# mkuBoard-044-3B.net
KiCad netlist of a schematic drawn in EAGLE
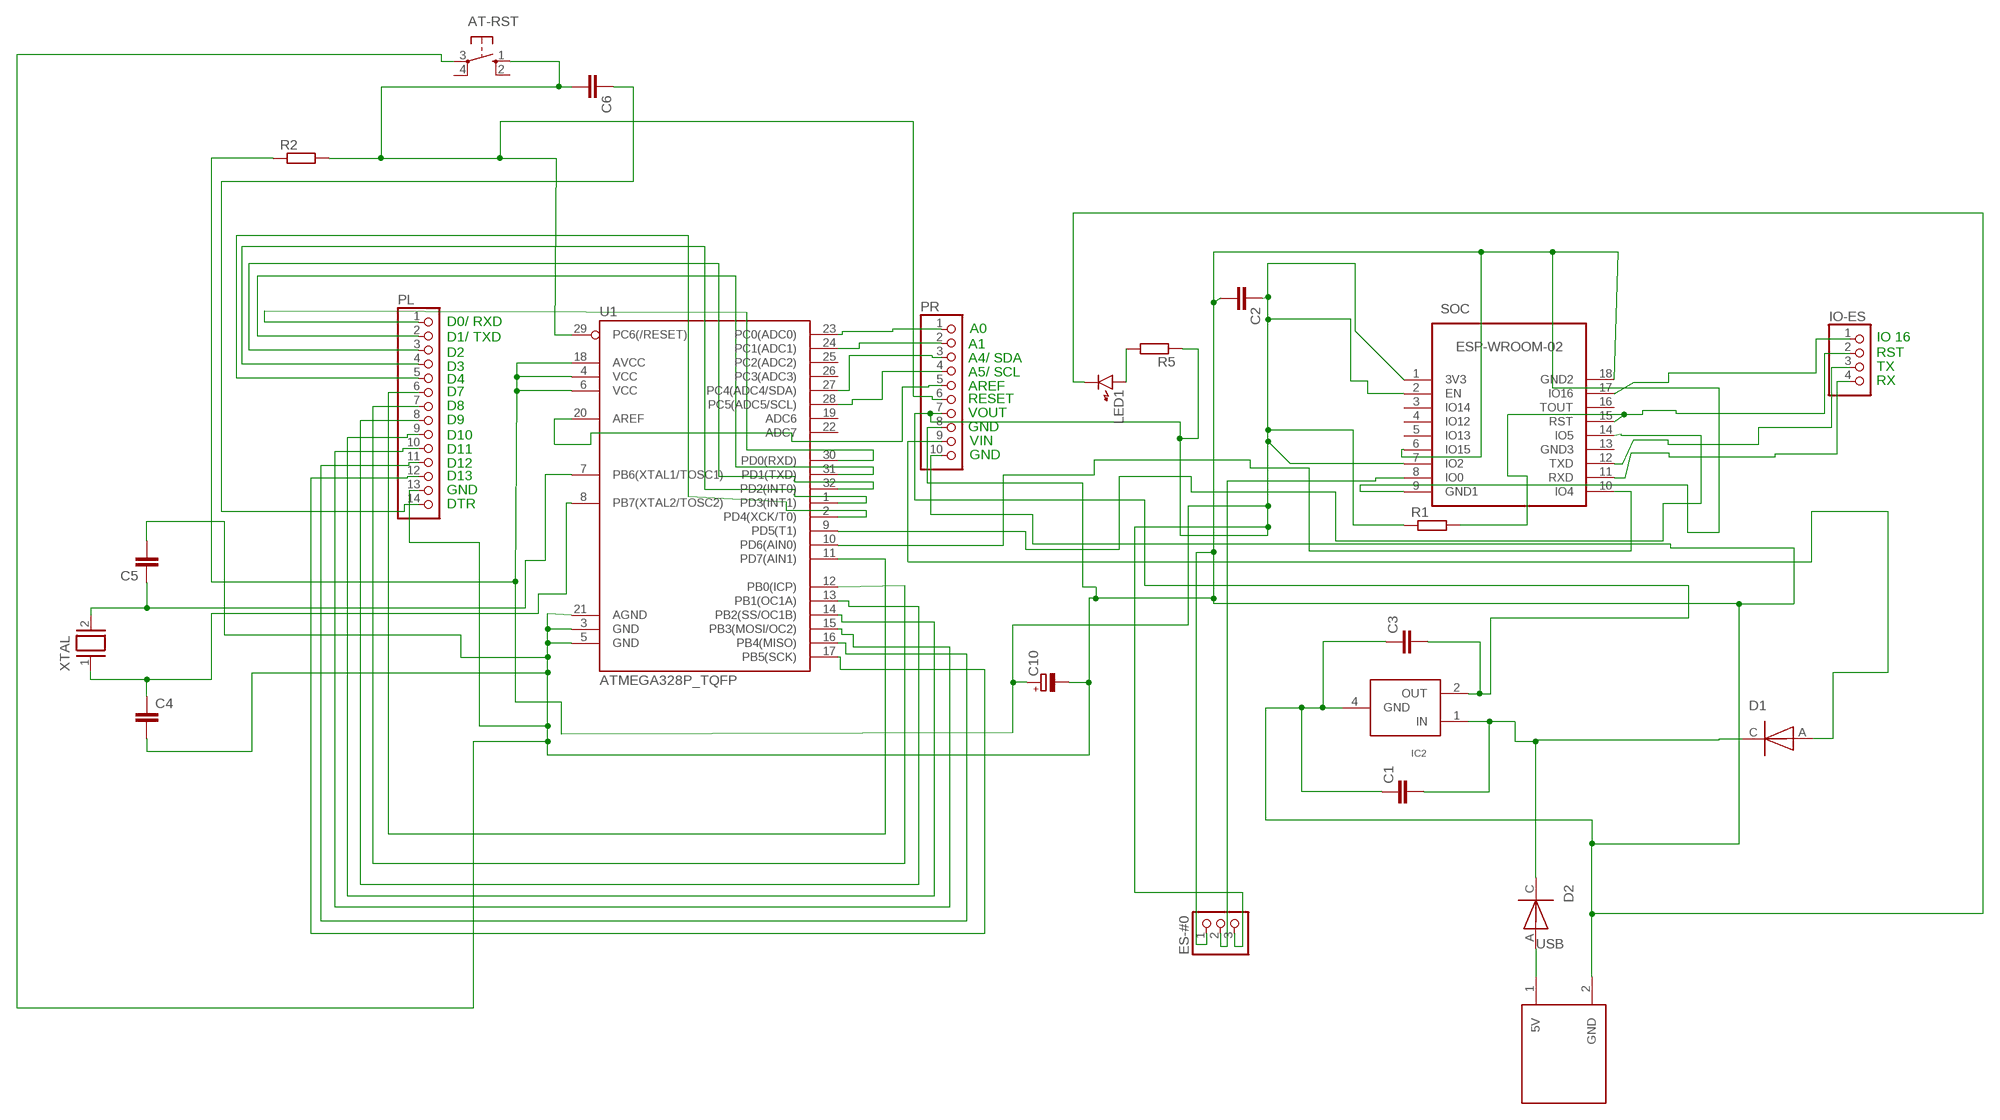
[diagram p0: schematic, sheet 1]

(export (version "E")
  (design (tool "Eeschema 10.0.6"))
  (components
    (comp (ref "AT-RST")
      (value "10-XX")
      (footprint "eagle-import:B3F-10XX")
      (fields (field (name "MPN") "B3F-1000"))
      (libsource (lib "eagle-import") (part "10-XX"))
    )
    (comp (ref "C1")
      (value "C-EUC0603")
      (footprint "eagle-import:C0603")
      (libsource (lib "eagle-import") (part "C-EUC0603"))
    )
    (comp (ref "C2")
      (value "C-EUC0603")
      (footprint "eagle-import:C0603")
      (libsource (lib "eagle-import") (part "C-EUC0603"))
    )
    (comp (ref "C3")
      (value "C-EUC1206")
      (footprint "eagle-import:C1206")
      (libsource (lib "eagle-import") (part "C-EUC1206"))
    )
    (comp (ref "C4")
      (value "C-EUC0603")
      (footprint "eagle-import:C0603")
      (libsource (lib "eagle-import") (part "C-EUC0603"))
    )
    (comp (ref "C5")
      (value "C-EUC0603")
      (footprint "eagle-import:C0603")
      (libsource (lib "eagle-import") (part "C-EUC0603"))
    )
    (comp (ref "C6")
      (value "C-EUC0603")
      (footprint "eagle-import:C0603")
      (libsource (lib "eagle-import") (part "C-EUC0603"))
    )
    (comp (ref "C10")
      (value "CPOL-EU153CLV-0605")
      (footprint "eagle-import:153CLV-0605")
      (libsource (lib "eagle-import") (part "CPOL-EU153CLV-0605"))
    )
    (comp (ref "D1")
      (value "DIODE-EX")
      (footprint "eagle-import:SOD80C")
      (libsource (lib "eagle-import") (part "DIODE-EX"))
    )
    (comp (ref "D2")
      (value "DIODE-EX")
      (footprint "eagle-import:SOD80C")
      (libsource (lib "eagle-import") (part "DIODE-EX"))
    )
    (comp (ref "ES-#0")
      (value "PINHD-1X3")
      (footprint "eagle-import:1X03")
      (libsource (lib "eagle-import") (part "PINHD-1X3"))
    )
    (comp (ref "IC2")
      (value "NJM2845DL1")
      (footprint "eagle-import:NJM2845DL1-PKG")
      (libsource (lib "eagle-import") (part "NJM2845DL1"))
    )
    (comp (ref "IO-ES")
      (value "PINHD-1X4")
      (footprint "eagle-import:1X04")
      (libsource (lib "eagle-import") (part "PINHD-1X4"))
    )
    (comp (ref "LED1")
      (value "LED1608")
      (footprint "eagle-import:LED1608")
      (libsource (lib "eagle-import") (part "LED1608"))
    )
    (comp (ref "PL")
      (value "PINHD-1X14")
      (footprint "eagle-import:1X14")
      (libsource (lib "eagle-import") (part "PINHD-1X14"))
    )
    (comp (ref "PR")
      (value "PINHD-1X10")
      (footprint "eagle-import:1X10")
      (libsource (lib "eagle-import") (part "PINHD-1X10"))
    )
    (comp (ref "R1")
      (value "R-EU_R0603")
      (footprint "eagle-import:R0603")
      (libsource (lib "eagle-import") (part "R-EU_R0603"))
    )
    (comp (ref "R2")
      (value "R-EU_R0603")
      (footprint "eagle-import:R0603")
      (libsource (lib "eagle-import") (part "R-EU_R0603"))
    )
    (comp (ref "R5")
      (value "R-EU_R0603")
      (footprint "eagle-import:R0603")
      (libsource (lib "eagle-import") (part "R-EU_R0603"))
    )
    (comp (ref "SOC")
      (value "ESP-WROOM-02")
      (footprint "eagle-import:FRONT-FACE-CP2")
      (libsource (lib "eagle-import") (part "ESP-WROOM-02-CP2FRONT"))
    )
    (comp (ref "U1")
      (value "ATMEGA328P_TQFP")
      (footprint "eagle-import:TQFP32-08")
      (libsource (lib "eagle-import") (part "ATMEGA328P_TQFP"))
    )
    (comp (ref "USB")
      (value "USB-CUST-1")
      (footprint "eagle-import:USB-CUST-1-PKG")
      (libsource (lib "eagle-import") (part "USB-CUST-1"))
    )
    (comp (ref "XTAL")
      (value "XTAL/S")
      (footprint "eagle-import:QS")
      (libsource (lib "eagle-import") (part "XTAL/S"))
    )
  )
  (nets
    (net (code "1") (name "Net-(AT-RST-P)") (class "Default")
      (node (ref "AT-RST") (pin "3") (pinfunction "P_3") (pintype "passive"))
      (node (ref "C1") (pin "1") (pinfunction "1_1") (pintype "passive"))
      (node (ref "C10") (pin "-") (pinfunction "-_-") (pintype "passive"))
      (node (ref "C2") (pin "2") (pinfunction "2_2") (pintype "passive"))
      (node (ref "C3") (pin "1") (pinfunction "1_1") (pintype "passive"))
      (node (ref "C4") (pin "2") (pinfunction "2_2") (pintype "passive"))
      (node (ref "C5") (pin "2") (pinfunction "2_2") (pintype "passive"))
      (node (ref "ES-#0") (pin "1") (pinfunction "1_1") (pintype "passive"))
      (node (ref "IC2") (pin "4") (pinfunction "GND_4") (pintype "bidirectional"))
      (node (ref "LED1") (pin "K") (pinfunction "K_K") (pintype "passive"))
      (node (ref "PL") (pin "13") (pinfunction "13_13") (pintype "passive"))
      (node (ref "PR") (pin "10") (pinfunction "10_10") (pintype "passive"))
      (node (ref "PR") (pin "8") (pinfunction "8_8") (pintype "passive"))
      (node (ref "SOC") (pin "18") (pinfunction "GND2_18") (pintype "bidirectional"))
      (node (ref "SOC") (pin "6") (pinfunction "IO15_6") (pintype "bidirectional"))
      (node (ref "SOC") (pin "9") (pinfunction "GND1_9") (pintype "bidirectional"))
      (node (ref "U1") (pin "21") (pinfunction "AGND_21") (pintype "bidirectional"))
      (node (ref "U1") (pin "3") (pinfunction "GND_3") (pintype "bidirectional"))
      (node (ref "U1") (pin "5") (pinfunction "GND_5") (pintype "bidirectional"))
      (node (ref "USB") (pin "2") (pinfunction "GND_2") (pintype "bidirectional"))
    )
    (net (code "2") (name "Net-(AT-RST-S)") (class "Default")
      (node (ref "AT-RST") (pin "1") (pinfunction "S_1") (pintype "passive"))
      (node (ref "C6") (pin "2") (pinfunction "2_2") (pintype "passive"))
      (node (ref "PR") (pin "6") (pinfunction "6_6") (pintype "passive"))
      (node (ref "R2") (pin "2") (pinfunction "2_2") (pintype "passive"))
      (node (ref "U1") (pin "29") (pinfunction "PC6(/RESET)_29") (pintype "bidirectional"))
    )
    (net (code "3") (name "Net-(C6-Pad1)") (class "Default")
      (node (ref "C6") (pin "1") (pinfunction "1_1") (pintype "passive"))
      (node (ref "PL") (pin "14") (pinfunction "14_14") (pintype "passive"))
    )
    (net (code "4") (name "Net-(D1-PadA)") (class "Default")
      (node (ref "D1") (pin "A") (pinfunction "A_A") (pintype "bidirectional"))
      (node (ref "PR") (pin "9") (pinfunction "9_9") (pintype "passive"))
    )
    (net (code "5") (name "Net-(IC2-IN)") (class "Default")
      (node (ref "C1") (pin "2") (pinfunction "2_2") (pintype "passive"))
      (node (ref "D1") (pin "C") (pinfunction "C_C") (pintype "bidirectional"))
      (node (ref "D2") (pin "C") (pinfunction "C_C") (pintype "bidirectional"))
      (node (ref "IC2") (pin "1") (pinfunction "IN_1") (pintype "bidirectional"))
    )
    (net (code "6") (name "Net-(IC2-OUT)") (class "Default")
      (node (ref "C10") (pin "+") (pinfunction "+_+") (pintype "passive"))
      (node (ref "C2") (pin "1") (pinfunction "1_1") (pintype "passive"))
      (node (ref "C3") (pin "2") (pinfunction "2_2") (pintype "passive"))
      (node (ref "ES-#0") (pin "3") (pinfunction "3_3") (pintype "passive"))
      (node (ref "IC2") (pin "2") (pinfunction "OUT_2") (pintype "bidirectional"))
      (node (ref "PR") (pin "7") (pinfunction "7_7") (pintype "passive"))
      (node (ref "R1") (pin "1") (pinfunction "1_1") (pintype "passive"))
      (node (ref "R2") (pin "1") (pinfunction "1_1") (pintype "passive"))
      (node (ref "R5") (pin "1") (pinfunction "1_1") (pintype "passive"))
      (node (ref "SOC") (pin "1") (pinfunction "3V3_1") (pintype "bidirectional"))
      (node (ref "SOC") (pin "2") (pinfunction "EN_2") (pintype "bidirectional"))
      (node (ref "SOC") (pin "7") (pinfunction "IO2_7") (pintype "bidirectional"))
      (node (ref "U1") (pin "18") (pinfunction "AVCC_18") (pintype "bidirectional"))
      (node (ref "U1") (pin "4") (pinfunction "VCC_4") (pintype "bidirectional"))
      (node (ref "U1") (pin "6") (pinfunction "VCC_6") (pintype "bidirectional"))
    )
    (net (code "7") (name "Net-(LED1-PadA)") (class "Default")
      (node (ref "LED1") (pin "A") (pinfunction "A_A") (pintype "passive"))
      (node (ref "R5") (pin "2") (pinfunction "2_2") (pintype "passive"))
    )
    (net (code "8") (name "Net-(SOC-IO0)") (class "Default")
      (node (ref "ES-#0") (pin "2") (pinfunction "2_2") (pintype "passive"))
      (node (ref "SOC") (pin "8") (pinfunction "IO0_8") (pintype "bidirectional"))
    )
    (net (code "9") (name "Net-(SOC-IO4)") (class "Default")
      (node (ref "SOC") (pin "10") (pinfunction "IO4_10") (pintype "bidirectional"))
      (node (ref "U1") (pin "10") (pinfunction "PD6(AIN0)_10") (pintype "bidirectional"))
    )
    (net (code "10") (name "Net-(SOC-IO5)") (class "Default")
      (node (ref "SOC") (pin "14") (pinfunction "IO5_14") (pintype "bidirectional"))
      (node (ref "U1") (pin "9") (pinfunction "PD5(T1)_9") (pintype "bidirectional"))
    )
    (net (code "11") (name "Net-(SOC-IO16)") (class "Default")
      (node (ref "IO-ES") (pin "1") (pinfunction "1_1") (pintype "passive"))
      (node (ref "SOC") (pin "17") (pinfunction "IO16_17") (pintype "bidirectional"))
    )
    (net (code "12") (name "Net-(SOC-RST)") (class "Default")
      (node (ref "IO-ES") (pin "2") (pinfunction "2_2") (pintype "passive"))
      (node (ref "R1") (pin "2") (pinfunction "2_2") (pintype "passive"))
      (node (ref "SOC") (pin "15") (pinfunction "RST_15") (pintype "bidirectional"))
    )
    (net (code "13") (name "Net-(SOC-RXD)") (class "Default")
      (node (ref "IO-ES") (pin "4") (pinfunction "4_4") (pintype "passive"))
      (node (ref "SOC") (pin "11") (pinfunction "RXD_11") (pintype "bidirectional"))
    )
    (net (code "14") (name "Net-(SOC-TXD)") (class "Default")
      (node (ref "IO-ES") (pin "3") (pinfunction "3_3") (pintype "passive"))
      (node (ref "SOC") (pin "12") (pinfunction "TXD_12") (pintype "bidirectional"))
    )
    (net (code "15") (name "Net-(U1-AREF)") (class "Default")
      (node (ref "PR") (pin "5") (pinfunction "5_5") (pintype "passive"))
      (node (ref "U1") (pin "20") (pinfunction "AREF_20") (pintype "bidirectional"))
    )
    (net (code "16") (name "Net-(U1-PB0(ICP))") (class "Default")
      (node (ref "PL") (pin "7") (pinfunction "7_7") (pintype "passive"))
      (node (ref "U1") (pin "12") (pinfunction "PB0(ICP)_12") (pintype "bidirectional"))
    )
    (net (code "17") (name "Net-(U1-PB1(OC1A))") (class "Default")
      (node (ref "PL") (pin "8") (pinfunction "8_8") (pintype "passive"))
      (node (ref "U1") (pin "13") (pinfunction "PB1(OC1A)_13") (pintype "bidirectional"))
    )
    (net (code "18") (name "Net-(U1-PB2(SS{slash}OC1B))") (class "Default")
      (node (ref "PL") (pin "9") (pinfunction "9_9") (pintype "passive"))
      (node (ref "U1") (pin "14") (pinfunction "PB2(SS/OC1B)_14") (pintype "bidirectional"))
    )
    (net (code "19") (name "Net-(U1-PB3(MOSI{slash}OC2))") (class "Default")
      (node (ref "PL") (pin "10") (pinfunction "10_10") (pintype "passive"))
      (node (ref "U1") (pin "15") (pinfunction "PB3(MOSI/OC2)_15") (pintype "bidirectional"))
    )
    (net (code "20") (name "Net-(U1-PB4(MISO))") (class "Default")
      (node (ref "PL") (pin "11") (pinfunction "11_11") (pintype "passive"))
      (node (ref "U1") (pin "16") (pinfunction "PB4(MISO)_16") (pintype "bidirectional"))
    )
    (net (code "21") (name "Net-(U1-PB5(SCK))") (class "Default")
      (node (ref "PL") (pin "12") (pinfunction "12_12") (pintype "passive"))
      (node (ref "U1") (pin "17") (pinfunction "PB5(SCK)_17") (pintype "bidirectional"))
    )
    (net (code "22") (name "Net-(U1-PB6(XTAL1{slash}TOSC1))") (class "Default")
      (node (ref "C5") (pin "1") (pinfunction "1_1") (pintype "passive"))
      (node (ref "U1") (pin "7") (pinfunction "PB6(XTAL1/TOSC1)_7") (pintype "bidirectional"))
      (node (ref "XTAL") (pin "2") (pinfunction "2_2") (pintype "passive"))
    )
    (net (code "23") (name "Net-(U1-PB7(XTAL2{slash}TOSC2))") (class "Default")
      (node (ref "C4") (pin "1") (pinfunction "1_1") (pintype "passive"))
      (node (ref "U1") (pin "8") (pinfunction "PB7(XTAL2/TOSC2)_8") (pintype "bidirectional"))
      (node (ref "XTAL") (pin "1") (pinfunction "1_1") (pintype "passive"))
    )
    (net (code "24") (name "Net-(U1-PC0(ADC0))") (class "Default")
      (node (ref "PR") (pin "1") (pinfunction "1_1") (pintype "passive"))
      (node (ref "U1") (pin "23") (pinfunction "PC0(ADC0)_23") (pintype "bidirectional"))
    )
    (net (code "25") (name "Net-(U1-PC1(ADC1))") (class "Default")
      (node (ref "PR") (pin "2") (pinfunction "2_2") (pintype "passive"))
      (node (ref "U1") (pin "24") (pinfunction "PC1(ADC1)_24") (pintype "bidirectional"))
    )
    (net (code "26") (name "Net-(U1-PC4(ADC4{slash}SDA))") (class "Default")
      (node (ref "PR") (pin "3") (pinfunction "3_3") (pintype "passive"))
      (node (ref "U1") (pin "27") (pinfunction "PC4(ADC4/SDA)_27") (pintype "bidirectional"))
    )
    (net (code "27") (name "Net-(U1-PC5(ADC5{slash}SCL))") (class "Default")
      (node (ref "PR") (pin "4") (pinfunction "4_4") (pintype "passive"))
      (node (ref "U1") (pin "28") (pinfunction "PC5(ADC5/SCL)_28") (pintype "bidirectional"))
    )
    (net (code "28") (name "Net-(U1-PD0(RXD))") (class "Default")
      (node (ref "PL") (pin "1") (pinfunction "1_1") (pintype "passive"))
      (node (ref "U1") (pin "30") (pinfunction "PD0(RXD)_30") (pintype "bidirectional"))
    )
    (net (code "29") (name "Net-(U1-PD1(TXD))") (class "Default")
      (node (ref "PL") (pin "2") (pinfunction "2_2") (pintype "passive"))
      (node (ref "U1") (pin "31") (pinfunction "PD1(TXD)_31") (pintype "bidirectional"))
    )
    (net (code "30") (name "Net-(U1-PD2(INT0))") (class "Default")
      (node (ref "PL") (pin "3") (pinfunction "3_3") (pintype "passive"))
      (node (ref "U1") (pin "32") (pinfunction "PD2(INT0)_32") (pintype "bidirectional"))
    )
    (net (code "31") (name "Net-(U1-PD3(INT1))") (class "Default")
      (node (ref "PL") (pin "4") (pinfunction "4_4") (pintype "passive"))
      (node (ref "U1") (pin "1") (pinfunction "PD3(INT1)_1") (pintype "bidirectional"))
    )
    (net (code "32") (name "Net-(U1-PD4(XCK{slash}T0))") (class "Default")
      (node (ref "PL") (pin "5") (pinfunction "5_5") (pintype "passive"))
      (node (ref "U1") (pin "2") (pinfunction "PD4(XCK/T0)_2") (pintype "bidirectional"))
    )
    (net (code "33") (name "Net-(U1-PD7(AIN1))") (class "Default")
      (node (ref "PL") (pin "6") (pinfunction "6_6") (pintype "passive"))
      (node (ref "U1") (pin "11") (pinfunction "PD7(AIN1)_11") (pintype "bidirectional"))
    )
    (net (code "34") (name "Net-(USB-5V)") (class "Default")
      (node (ref "D2") (pin "A") (pinfunction "A_A") (pintype "bidirectional"))
      (node (ref "USB") (pin "1") (pinfunction "5V_1") (pintype "bidirectional"))
    )
    (net (code "35") (name "unconnected-(AT-RST-P1-Pad4)") (class "Default")
      (node (ref "AT-RST") (pin "4") (pinfunction "P1_4") (pintype "passive"))
    )
    (net (code "36") (name "unconnected-(AT-RST-S1-Pad2)") (class "Default")
      (node (ref "AT-RST") (pin "2") (pinfunction "S1_2") (pintype "passive"))
    )
    (net (code "37") (name "unconnected-(SOC-GND3-Pad13)") (class "Default")
      (node (ref "SOC") (pin "13") (pinfunction "GND3_13") (pintype "bidirectional"))
    )
    (net (code "38") (name "unconnected-(SOC-IO12-Pad4)") (class "Default")
      (node (ref "SOC") (pin "4") (pinfunction "IO12_4") (pintype "bidirectional"))
    )
    (net (code "39") (name "unconnected-(SOC-IO13-Pad5)") (class "Default")
      (node (ref "SOC") (pin "5") (pinfunction "IO13_5") (pintype "open_collector"))
    )
    (net (code "40") (name "unconnected-(SOC-IO14-Pad3)") (class "Default")
      (node (ref "SOC") (pin "3") (pinfunction "IO14_3") (pintype "bidirectional"))
    )
    (net (code "41") (name "unconnected-(SOC-TOUT-Pad16)") (class "Default")
      (node (ref "SOC") (pin "16") (pinfunction "TOUT_16") (pintype "bidirectional"))
    )
    (net (code "42") (name "unconnected-(U1-ADC6-Pad19)") (class "Default")
      (node (ref "U1") (pin "19") (pinfunction "ADC6_19") (pintype "bidirectional"))
    )
    (net (code "43") (name "unconnected-(U1-ADC7-Pad22)") (class "Default")
      (node (ref "U1") (pin "22") (pinfunction "ADC7_22") (pintype "bidirectional"))
    )
    (net (code "44") (name "unconnected-(U1-PC2(ADC2)-Pad25)") (class "Default")
      (node (ref "U1") (pin "25") (pinfunction "PC2(ADC2)_25") (pintype "bidirectional"))
    )
    (net (code "45") (name "unconnected-(U1-PC3(ADC3)-Pad26)") (class "Default")
      (node (ref "U1") (pin "26") (pinfunction "PC3(ADC3)_26") (pintype "bidirectional"))
    )
  )
)
